# LARIX_V5_0.net
KiCad netlist of a schematic drawn in Altium Designer
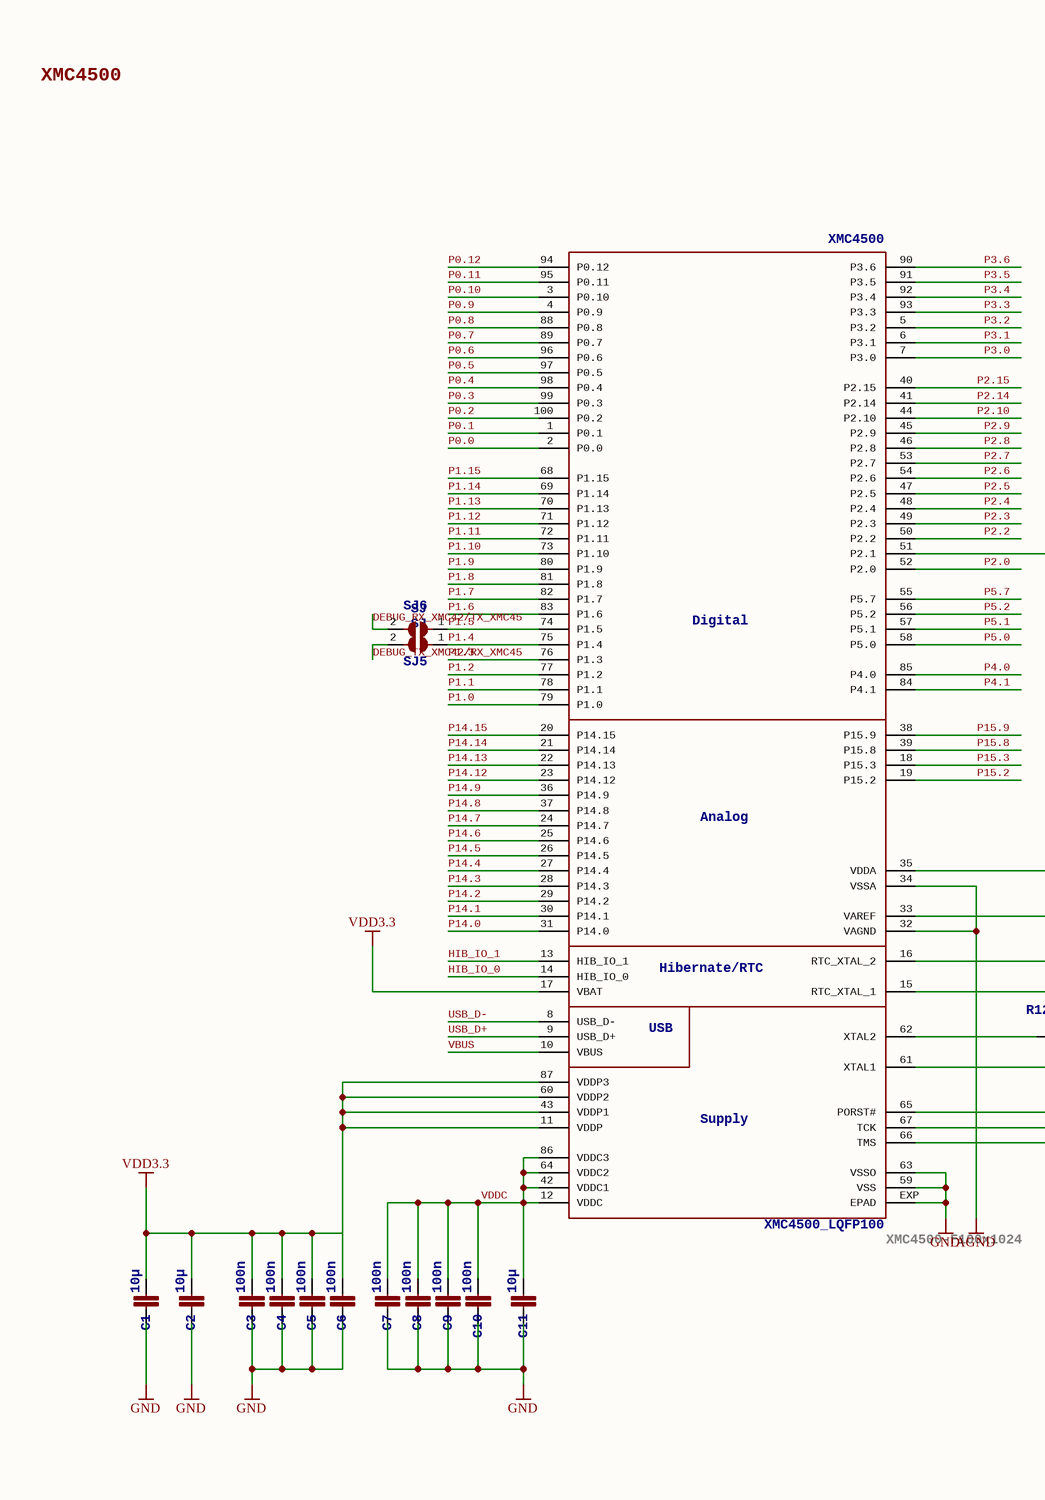
[diagram p0: LARIX_V5_0.SchDoc, left]
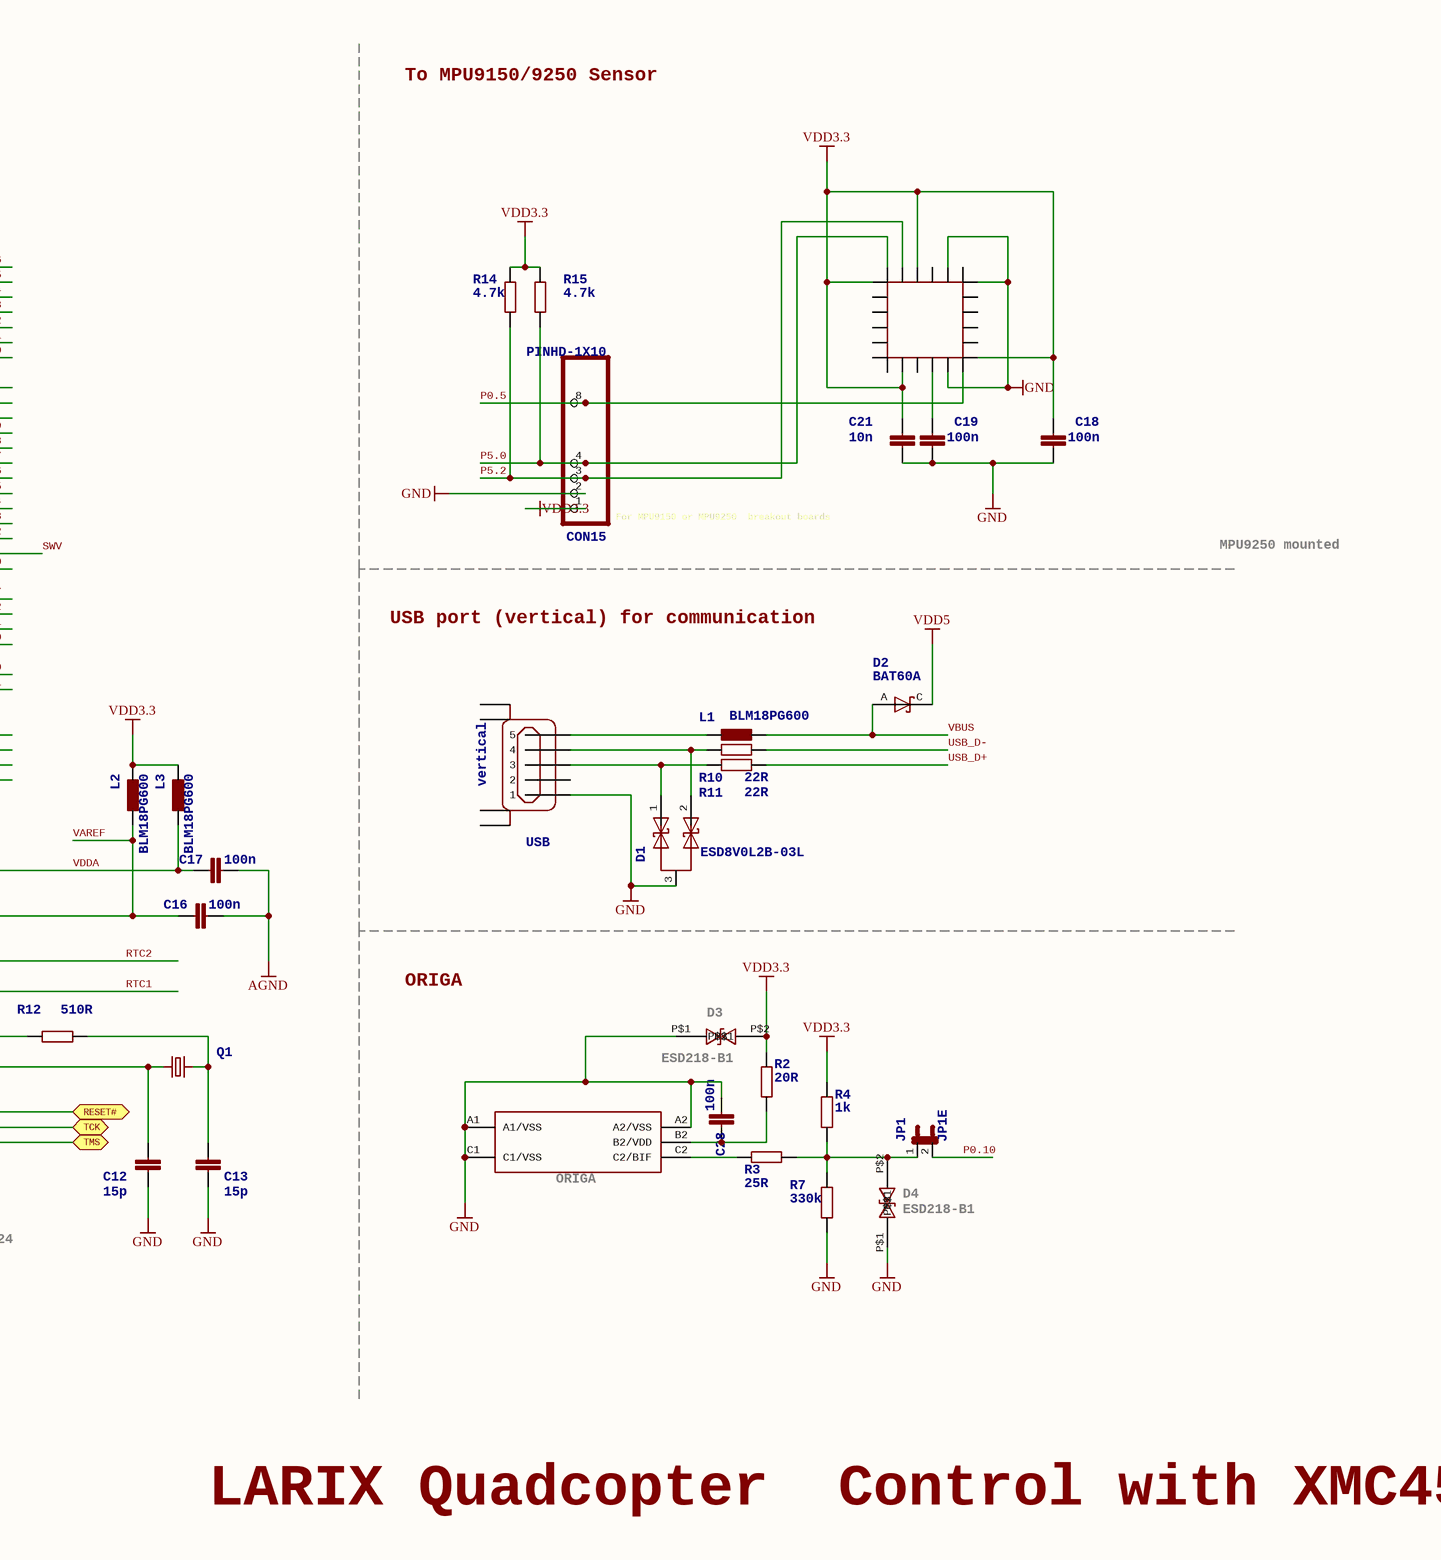
[diagram p1: LARIX_V5_0.SchDoc, right]

(export (version "E")
  (design (tool "Eeschema 10.0.6"))
  (components
    (comp (ref "C1")
      (value "10µ")
      (footprint "C0805K")
      (description "<B>CAPACITOR</B>, European symbol")
      (libsource (lib "libHMI_OLED-V1") (part "C-EUC0805K"))
    )
    (comp (ref "C2")
      (value "10µ")
      (footprint "C0805K")
      (description "<B>CAPACITOR</B>, European symbol")
      (libsource (lib "libHMI_OLED-V1") (part "C-EUC0805K"))
    )
    (comp (ref "C3")
      (value "100n")
      (footprint "C0603")
      (description "<B>CAPACITOR</B>, European symbol")
      (libsource (lib "libresistor") (part "C-EUC0603"))
    )
    (comp (ref "C4")
      (value "100n")
      (footprint "C0603")
      (description "<B>CAPACITOR</B>, European symbol")
      (libsource (lib "libresistor") (part "C-EUC0603"))
    )
    (comp (ref "C5")
      (value "100n")
      (footprint "C0603")
      (description "<B>CAPACITOR</B>, European symbol")
      (libsource (lib "libresistor") (part "C-EUC0603"))
    )
    (comp (ref "C6")
      (value "100n")
      (footprint "C0603")
      (description "<B>CAPACITOR</B>, European symbol")
      (libsource (lib "libresistor") (part "C-EUC0603"))
    )
    (comp (ref "C7")
      (value "100n")
      (footprint "C0603")
      (description "<B>CAPACITOR</B>, European symbol")
      (libsource (lib "libresistor") (part "C-EUC0603"))
    )
    (comp (ref "C8")
      (value "100n")
      (footprint "C0603")
      (description "<B>CAPACITOR</B>, European symbol")
      (libsource (lib "libresistor") (part "C-EUC0603"))
    )
    (comp (ref "C9")
      (value "100n")
      (footprint "C0603")
      (description "<B>CAPACITOR</B>, European symbol")
      (libsource (lib "libresistor") (part "C-EUC0603"))
    )
    (comp (ref "C10")
      (value "100n")
      (footprint "C0603")
      (description "<B>CAPACITOR</B>, European symbol")
      (libsource (lib "libresistor") (part "C-EUC0603"))
    )
    (comp (ref "C11")
      (value "10µ")
      (footprint "C0805K")
      (description "<B>CAPACITOR</B>, European symbol")
      (libsource (lib "libHMI_OLED-V1") (part "C-EUC0805K"))
    )
    (comp (ref "C12")
      (value "15p")
      (footprint "C0603")
      (description "<B>CAPACITOR</B>, European symbol")
      (libsource (lib "libresistor") (part "C-EUC0603"))
    )
    (comp (ref "C13")
      (value "15p")
      (footprint "C0603")
      (description "<B>CAPACITOR</B>, European symbol")
      (libsource (lib "libresistor") (part "C-EUC0603"))
    )
    (comp (ref "C16")
      (value "100n")
      (footprint "C0603")
      (description "<B>CAPACITOR</B>, European symbol")
      (libsource (lib "") (part "C-EUC0603_2"))
    )
    (comp (ref "C17")
      (value "100n")
      (footprint "C0603")
      (description "<B>CAPACITOR</B>, European symbol")
      (libsource (lib "") (part "C-EUC0603_2"))
    )
    (comp (ref "C18")
      (value "100n")
      (footprint "C0603")
      (description "<B>CAPACITOR</B>, European symbol")
      (libsource (lib "") (part "C-EUC0603_1"))
    )
    (comp (ref "C19")
      (value "100n")
      (footprint "C0603")
      (description "<B>CAPACITOR</B>, European symbol")
      (libsource (lib "") (part "C-EUC0603_1"))
    )
    (comp (ref "C21")
      (value "10n")
      (footprint "C0603")
      (description "<B>CAPACITOR</B>, European symbol")
      (libsource (lib "") (part "C-EUC0603_1"))
    )
    (comp (ref "C28")
      (value "100n")
      (footprint "C0603")
      (description "<B>CAPACITOR</B>, European symbol")
      (libsource (lib "libresistor") (part "C-EUC0603"))
    )
    (comp (ref "CON15")
      (value "PINHD-1X10")
      (footprint "1X10")
      (description "<b>PIN HEADER</b>")
      (fields (field (name ">NAME") "CON15") (field (name ">VALUE") "PINHD-1X10"))
      (libsource (lib "pinhead") (part "PINHD-1X10"))
    )
    (comp (ref "D1")
      (value "ESD8V0L2B-03L")
      (footprint "TSLP-3-1")
      (libsource (lib "libDsDiod") (part "ESD8V0L2B-03L"))
    )
    (comp (ref "D2") (value "BAT60A") (footprint "SOD323-R") (libsource (lib "libDsDiod") (part "BAT60")))
    (comp (ref "D3")
      (value "ESD218-B1-02EL")
      (footprint "TSLP-2-20")
      (libsource (lib "libESD218-B1") (part "ESD218-B1-02EL"))
    )
    (comp (ref "D4")
      (value "ESD218-B1-02EL")
      (footprint "TSLP-2-20")
      (libsource (lib "libESD218-B1") (part "ESD218-B1-02EL"))
    )
    (comp (ref "JP1")
      (value "JP1E")
      (footprint "JP1")
      (description "<b>JUMPER</b>")
      (fields (field (name ">NAME") "JP1") (field (name ">VALUE") "JP1E"))
      (libsource (lib "jumper") (part "JP1E"))
    )
    (comp (ref "L1") (value "BLM18PG600") (footprint "L1608") (libsource (lib "") (part "L_EU_L0603_1")))
    (comp (ref "L2")
      (value "BLM18PG600")
      (footprint "L1608")
      (fields (field (name ">NAME") "L2") (field (name ">VALUE") "BLM18PG600"))
      (libsource (lib "libPDFerr") (part "L_EU_L0603"))
    )
    (comp (ref "L3")
      (value "BLM18PG600")
      (footprint "L1608")
      (fields (field (name ">NAME") "L3") (field (name ">VALUE") "BLM18PG600"))
      (libsource (lib "libPDFerr") (part "L_EU_L0603"))
    )
    (comp (ref "MPU9250")
      (value "MPU9250")
      (footprint "QFN3X3-24+")
      (description "Herbys Model of a invensense 9250")
      (libsource (lib "invensense9250") (part "INVENSENSE9250HERBY"))
    )
    (comp (ref "ORIGA") (value "ORIGA2L") (footprint "WLB-5") (libsource (lib "libORIGA") (part "ORIGA2L")))
    (comp (ref "Q1")
      (value "12MHZ/S/3.2X2.5")
      (footprint "32X25_4PAD")
      (libsource (lib "libXMC4500_Relax-V1+USBvertical") (part "NX3225_2"))
    )
    (comp (ref "R2") (value "20R") (footprint "R0603") (libsource (lib "libDsR") (part "R-EU_R0603")))
    (comp (ref "R3") (value "25R") (footprint "R0603") (libsource (lib "libDsR") (part "R-EU_R0603")))
    (comp (ref "R4") (value "1k") (footprint "R0603") (libsource (lib "libDsR") (part "R-EU_R0603")))
    (comp (ref "R7") (value "330k") (footprint "R0603") (libsource (lib "libDsR") (part "R-EU_R0603")))
    (comp (ref "R10")
      (value "22R")
      (footprint "R0603")
      (description "<B>RESISTOR</B>, European symbol")
      (libsource (lib "libresistor") (part "R-EU_R0603"))
    )
    (comp (ref "R11")
      (value "22R")
      (footprint "R0603")
      (description "<B>RESISTOR</B>, European symbol")
      (libsource (lib "libresistor") (part "R-EU_R0603"))
    )
    (comp (ref "R12") (value "510R") (footprint "R0603") (libsource (lib "libDsR") (part "R-EU_R0603")))
    (comp (ref "R14")
      (value "4.7k")
      (footprint "R0603")
      (description "<B>RESISTOR</B>, European symbol")
      (libsource (lib "libresistor") (part "R-EU_R0603"))
    )
    (comp (ref "R15")
      (value "4.7k")
      (footprint "R0603")
      (description "<B>RESISTOR</B>, European symbol")
      (libsource (lib "libresistor") (part "R-EU_R0603"))
    )
    (comp (ref "SJ5")
      (value "SJ")
      (footprint "SJ")
      (description "SMD solder <b>JUMPER</b>")
      (libsource (lib "jumper") (part "SJ"))
    )
    (comp (ref "SJ6")
      (value "SJ")
      (footprint "SJ")
      (description "SMD solder <b>JUMPER</b>")
      (libsource (lib "jumper") (part "SJ"))
    )
    (comp (ref "USB")
      (value "vertical")
      (footprint "USBVERTICAL")
      (libsource (lib "libXMC4500_Relax-V1+USBvertical") (part "MICRO_USB_VERTICAL"))
    )
    (comp (ref "XMC4500")
      (value "XMC4500_LQFP100")
      (footprint "P/PG-LQFP-100-11")
      (fields
        (field (name ">NAME") "XMC4500")
        (field (name ">VALUE") "XMC4500_LQFP100")
        (field (name "USB") "USB")
        (field (name "SUPPLY") "Supply")
        (field (name "ANALOG") "Analog")
        (field (name "DIGITAL") "Digital")
        (field (name "HIBERNATE/RTC") "Hibernate/RTC")
      )
      (libsource (lib "libXMC4500_Relax-V1+USBvertical") (part "XMC4400_LQFP100"))
    )
  )
  (nets
    (net (code "1") (name "/DEBUG_RX_XMC42{slash}TX_XMC45") (class "Default")
      (node (ref "SJ6") (pin "2") (pinfunction "2_2") (pintype "passive"))
    )
    (net (code "2") (name "/DEBUG_TX_XMC42{slash}RX_XMC45") (class "Default")
      (node (ref "SJ5") (pin "2") (pinfunction "2_2") (pintype "passive"))
    )
    (net (code "3") (name "/HIB_IO_0") (class "Default")
      (node (ref "XMC4500") (pin "14") (pinfunction "HIB_IO_0_14") (pintype "passive"))
    )
    (net (code "4") (name "/HIB_IO_1") (class "Default")
      (node (ref "XMC4500") (pin "13") (pinfunction "HIB_IO_1_13") (pintype "passive"))
    )
    (net (code "5") (name "/P0.0") (class "Default")
      (node (ref "XMC4500") (pin "2") (pinfunction "P0.0_2") (pintype "passive"))
    )
    (net (code "6") (name "/P0.1") (class "Default")
      (node (ref "XMC4500") (pin "1") (pinfunction "P0.1_1") (pintype "passive"))
    )
    (net (code "7") (name "/P0.2") (class "Default")
      (node (ref "XMC4500") (pin "100") (pinfunction "P0.2_100") (pintype "passive"))
    )
    (net (code "8") (name "/P0.3") (class "Default")
      (node (ref "XMC4500") (pin "99") (pinfunction "P0.3_99") (pintype "passive"))
    )
    (net (code "9") (name "/P0.4") (class "Default")
      (node (ref "XMC4500") (pin "98") (pinfunction "P0.4_98") (pintype "passive"))
    )
    (net (code "10") (name "/P0.5") (class "Default")
      (node (ref "CON15") (pin "8") (pinfunction "8_8") (pintype "passive"))
      (node (ref "MPU9250") (pin "12") (pinfunction "12_12") (pintype "passive"))
      (node (ref "XMC4500") (pin "97") (pinfunction "P0.5_97") (pintype "passive"))
    )
    (net (code "11") (name "/P0.6") (class "Default")
      (node (ref "XMC4500") (pin "96") (pinfunction "P0.6_96") (pintype "passive"))
    )
    (net (code "12") (name "/P0.7") (class "Default")
      (node (ref "XMC4500") (pin "89") (pinfunction "P0.7_89") (pintype "passive"))
    )
    (net (code "13") (name "/P0.8") (class "Default")
      (node (ref "XMC4500") (pin "88") (pinfunction "P0.8_88") (pintype "passive"))
    )
    (net (code "14") (name "/P0.9") (class "Default")
      (node (ref "XMC4500") (pin "4") (pinfunction "P0.9_4") (pintype "passive"))
    )
    (net (code "15") (name "/P0.10") (class "Default")
      (node (ref "JP1") (pin "2") (pinfunction "2_2") (pintype "passive"))
      (node (ref "XMC4500") (pin "3") (pinfunction "P0.10_3") (pintype "passive"))
    )
    (net (code "16") (name "/P0.11") (class "Default")
      (node (ref "XMC4500") (pin "95") (pinfunction "P0.11_95") (pintype "passive"))
    )
    (net (code "17") (name "/P0.12") (class "Default")
      (node (ref "XMC4500") (pin "94") (pinfunction "P0.12_94") (pintype "passive"))
    )
    (net (code "18") (name "/P1.0") (class "Default")
      (node (ref "XMC4500") (pin "79") (pinfunction "P1.0_79") (pintype "passive"))
    )
    (net (code "19") (name "/P1.1") (class "Default")
      (node (ref "XMC4500") (pin "78") (pinfunction "P1.1_78") (pintype "passive"))
    )
    (net (code "20") (name "/P1.2") (class "Default")
      (node (ref "XMC4500") (pin "77") (pinfunction "P1.2_77") (pintype "passive"))
    )
    (net (code "21") (name "/P1.3") (class "Default")
      (node (ref "XMC4500") (pin "76") (pinfunction "P1.3_76") (pintype "passive"))
    )
    (net (code "22") (name "/P1.4") (class "Default")
      (node (ref "SJ5") (pin "1") (pinfunction "1_1") (pintype "passive"))
      (node (ref "XMC4500") (pin "75") (pinfunction "P1.4_75") (pintype "passive"))
    )
    (net (code "23") (name "/P1.5") (class "Default")
      (node (ref "SJ6") (pin "1") (pinfunction "1_1") (pintype "passive"))
      (node (ref "XMC4500") (pin "74") (pinfunction "P1.5_74") (pintype "passive"))
    )
    (net (code "24") (name "/P1.6") (class "Default")
      (node (ref "XMC4500") (pin "83") (pinfunction "P1.6_83") (pintype "passive"))
    )
    (net (code "25") (name "/P1.7") (class "Default")
      (node (ref "XMC4500") (pin "82") (pinfunction "P1.7_82") (pintype "passive"))
    )
    (net (code "26") (name "/P1.8") (class "Default")
      (node (ref "XMC4500") (pin "81") (pinfunction "P1.8_81") (pintype "passive"))
    )
    (net (code "27") (name "/P1.9") (class "Default")
      (node (ref "XMC4500") (pin "80") (pinfunction "P1.9_80") (pintype "passive"))
    )
    (net (code "28") (name "/P1.10") (class "Default")
      (node (ref "XMC4500") (pin "73") (pinfunction "P1.10_73") (pintype "passive"))
    )
    (net (code "29") (name "/P1.11") (class "Default")
      (node (ref "XMC4500") (pin "72") (pinfunction "P1.11_72") (pintype "passive"))
    )
    (net (code "30") (name "/P1.12") (class "Default")
      (node (ref "XMC4500") (pin "71") (pinfunction "P1.12_71") (pintype "passive"))
    )
    (net (code "31") (name "/P1.13") (class "Default")
      (node (ref "XMC4500") (pin "70") (pinfunction "P1.13_70") (pintype "passive"))
    )
    (net (code "32") (name "/P1.14") (class "Default")
      (node (ref "XMC4500") (pin "69") (pinfunction "P1.14_69") (pintype "passive"))
    )
    (net (code "33") (name "/P1.15") (class "Default")
      (node (ref "XMC4500") (pin "68") (pinfunction "P1.15_68") (pintype "passive"))
    )
    (net (code "34") (name "/P2.0") (class "Default")
      (node (ref "XMC4500") (pin "52") (pinfunction "P2.0_52") (pintype "passive"))
    )
    (net (code "35") (name "/P2.2") (class "Default")
      (node (ref "XMC4500") (pin "50") (pinfunction "P2.2_50") (pintype "passive"))
    )
    (net (code "36") (name "/P2.3") (class "Default")
      (node (ref "XMC4500") (pin "49") (pinfunction "P2.3_49") (pintype "passive"))
    )
    (net (code "37") (name "/P2.4") (class "Default")
      (node (ref "XMC4500") (pin "48") (pinfunction "P2.4_48") (pintype "passive"))
    )
    (net (code "38") (name "/P2.5") (class "Default")
      (node (ref "XMC4500") (pin "47") (pinfunction "P2.5_47") (pintype "passive"))
    )
    (net (code "39") (name "/P2.6") (class "Default")
      (node (ref "XMC4500") (pin "54") (pinfunction "P2.6_54") (pintype "passive"))
    )
    (net (code "40") (name "/P2.7") (class "Default")
      (node (ref "XMC4500") (pin "53") (pinfunction "P2.7_53") (pintype "passive"))
    )
    (net (code "41") (name "/P2.8") (class "Default")
      (node (ref "XMC4500") (pin "46") (pinfunction "P2.8_46") (pintype "passive"))
    )
    (net (code "42") (name "/P2.9") (class "Default")
      (node (ref "XMC4500") (pin "45") (pinfunction "P2.9_45") (pintype "passive"))
    )
    (net (code "43") (name "/P2.10") (class "Default")
      (node (ref "XMC4500") (pin "44") (pinfunction "P2.10_44") (pintype "passive"))
    )
    (net (code "44") (name "/P2.14") (class "Default")
      (node (ref "XMC4500") (pin "41") (pinfunction "P2.14_41") (pintype "passive"))
    )
    (net (code "45") (name "/P2.15") (class "Default")
      (node (ref "XMC4500") (pin "40") (pinfunction "P2.15_40") (pintype "passive"))
    )
    (net (code "46") (name "/P3.0") (class "Default")
      (node (ref "XMC4500") (pin "7") (pinfunction "P3.0_7") (pintype "passive"))
    )
    (net (code "47") (name "/P3.1") (class "Default")
      (node (ref "XMC4500") (pin "6") (pinfunction "P3.1_6") (pintype "passive"))
    )
    (net (code "48") (name "/P3.2") (class "Default")
      (node (ref "XMC4500") (pin "5") (pinfunction "P3.2_5") (pintype "passive"))
    )
    (net (code "49") (name "/P3.3") (class "Default")
      (node (ref "XMC4500") (pin "93") (pinfunction "P3.3_93") (pintype "passive"))
    )
    (net (code "50") (name "/P3.4") (class "Default")
      (node (ref "XMC4500") (pin "92") (pinfunction "P3.4_92") (pintype "passive"))
    )
    (net (code "51") (name "/P3.5") (class "Default")
      (node (ref "XMC4500") (pin "91") (pinfunction "P3.5_91") (pintype "passive"))
    )
    (net (code "52") (name "/P3.6") (class "Default")
      (node (ref "XMC4500") (pin "90") (pinfunction "P3.6_90") (pintype "passive"))
    )
    (net (code "53") (name "/P4.0") (class "Default")
      (node (ref "XMC4500") (pin "85") (pinfunction "P4.0_85") (pintype "passive"))
    )
    (net (code "54") (name "/P4.1") (class "Default")
      (node (ref "XMC4500") (pin "84") (pinfunction "P4.1_84") (pintype "passive"))
    )
    (net (code "55") (name "/P5.0") (class "Default")
      (node (ref "CON15") (pin "4") (pinfunction "4_4") (pintype "passive"))
      (node (ref "MPU9250") (pin "24") (pinfunction "24_24") (pintype "passive"))
      (node (ref "R15") (pin "1") (pinfunction "1_1") (pintype "passive"))
      (node (ref "XMC4500") (pin "58") (pinfunction "P5.0_58") (pintype "passive"))
    )
    (net (code "56") (name "/P5.1") (class "Default")
      (node (ref "XMC4500") (pin "57") (pinfunction "P5.1_57") (pintype "passive"))
    )
    (net (code "57") (name "/P5.2") (class "Default")
      (node (ref "CON15") (pin "3") (pinfunction "3_3") (pintype "passive"))
      (node (ref "MPU9250") (pin "23") (pinfunction "23_23") (pintype "passive"))
      (node (ref "R14") (pin "1") (pinfunction "1_1") (pintype "passive"))
      (node (ref "XMC4500") (pin "56") (pinfunction "P5.2_56") (pintype "passive"))
    )
    (net (code "58") (name "/P5.7") (class "Default")
      (node (ref "XMC4500") (pin "55") (pinfunction "P5.7_55") (pintype "passive"))
    )
    (net (code "59") (name "/P14.0") (class "Default")
      (node (ref "XMC4500") (pin "31") (pinfunction "P14.0_31") (pintype "passive"))
    )
    (net (code "60") (name "/P14.1") (class "Default")
      (node (ref "XMC4500") (pin "30") (pinfunction "P14.1_30") (pintype "passive"))
    )
    (net (code "61") (name "/P14.2") (class "Default")
      (node (ref "XMC4500") (pin "29") (pinfunction "P14.2_29") (pintype "passive"))
    )
    (net (code "62") (name "/P14.3") (class "Default")
      (node (ref "XMC4500") (pin "28") (pinfunction "P14.3_28") (pintype "passive"))
    )
    (net (code "63") (name "/P14.4") (class "Default")
      (node (ref "XMC4500") (pin "27") (pinfunction "P14.4_27") (pintype "passive"))
    )
    (net (code "64") (name "/P14.5") (class "Default")
      (node (ref "XMC4500") (pin "26") (pinfunction "P14.5_26") (pintype "passive"))
    )
    (net (code "65") (name "/P14.6") (class "Default")
      (node (ref "XMC4500") (pin "25") (pinfunction "P14.6_25") (pintype "passive"))
    )
    (net (code "66") (name "/P14.7") (class "Default")
      (node (ref "XMC4500") (pin "24") (pinfunction "P14.7_24") (pintype "passive"))
    )
    (net (code "67") (name "/P14.8") (class "Default")
      (node (ref "XMC4500") (pin "37") (pinfunction "P14.8_37") (pintype "passive"))
    )
    (net (code "68") (name "/P14.9") (class "Default")
      (node (ref "XMC4500") (pin "36") (pinfunction "P14.9_36") (pintype "passive"))
    )
    (net (code "69") (name "/P14.12") (class "Default")
      (node (ref "XMC4500") (pin "23") (pinfunction "P14.12_23") (pintype "passive"))
    )
    (net (code "70") (name "/P14.13") (class "Default")
      (node (ref "XMC4500") (pin "22") (pinfunction "P14.13_22") (pintype "passive"))
    )
    (net (code "71") (name "/P14.14") (class "Default")
      (node (ref "XMC4500") (pin "21") (pinfunction "P14.14_21") (pintype "passive"))
    )
    (net (code "72") (name "/P14.15") (class "Default")
      (node (ref "XMC4500") (pin "20") (pinfunction "P14.15_20") (pintype "passive"))
    )
    (net (code "73") (name "/P15.2") (class "Default")
      (node (ref "XMC4500") (pin "19") (pinfunction "P15.2_19") (pintype "passive"))
    )
    (net (code "74") (name "/P15.3") (class "Default")
      (node (ref "XMC4500") (pin "18") (pinfunction "P15.3_18") (pintype "passive"))
    )
    (net (code "75") (name "/P15.8") (class "Default")
      (node (ref "XMC4500") (pin "39") (pinfunction "P15.8_39") (pintype "passive"))
    )
    (net (code "76") (name "/P15.9") (class "Default")
      (node (ref "XMC4500") (pin "38") (pinfunction "P15.9_38") (pintype "passive"))
    )
    (net (code "77") (name "/RESET#") (class "Default")
      (node (ref "XMC4500") (pin "65") (pinfunction "PORST#_65") (pintype "passive"))
    )
    (net (code "78") (name "/RTC1") (class "Default")
      (node (ref "XMC4500") (pin "15") (pinfunction "RTC_XTAL_1_15") (pintype "passive"))
    )
    (net (code "79") (name "/RTC2") (class "Default")
      (node (ref "XMC4500") (pin "16") (pinfunction "RTC_XTAL_2_16") (pintype "passive"))
    )
    (net (code "80") (name "/SWV") (class "Default")
      (node (ref "XMC4500") (pin "51") (pinfunction "P2.1_51") (pintype "passive"))
    )
    (net (code "81") (name "/TCK") (class "Default")
      (node (ref "XMC4500") (pin "67") (pinfunction "TCK_67") (pintype "passive"))
    )
    (net (code "82") (name "/TMS") (class "Default")
      (node (ref "XMC4500") (pin "66") (pinfunction "TMS_66") (pintype "passive"))
    )
    (net (code "83") (name "/USB_D+") (class "Default")
      (node (ref "R11") (pin "2") (pinfunction "2_2") (pintype "passive"))
      (node (ref "XMC4500") (pin "9") (pinfunction "USB_D+_9") (pintype "passive"))
    )
    (net (code "84") (name "/USB_D-") (class "Default")
      (node (ref "R10") (pin "2") (pinfunction "2_2") (pintype "passive"))
      (node (ref "XMC4500") (pin "8") (pinfunction "USB_D-_8") (pintype "passive"))
    )
    (net (code "85") (name "/VAREF") (class "Default")
      (node (ref "C16") (pin "1") (pinfunction "1_1") (pintype "passive"))
      (node (ref "L2") (pin "1") (pinfunction "1_1") (pintype "passive"))
      (node (ref "XMC4500") (pin "33") (pinfunction "VAREF_33") (pintype "passive"))
    )
    (net (code "86") (name "/VBUS") (class "Default")
      (node (ref "D2") (pin "A") (pinfunction "A_A") (pintype "passive"))
      (node (ref "L1") (pin "1") (pinfunction "1_1") (pintype "passive"))
      (node (ref "XMC4500") (pin "10") (pinfunction "VBUS_10") (pintype "passive"))
    )
    (net (code "87") (name "/VDDA") (class "Default")
      (node (ref "C17") (pin "1") (pinfunction "1_1") (pintype "passive"))
      (node (ref "L3") (pin "1") (pinfunction "1_1") (pintype "passive"))
      (node (ref "XMC4500") (pin "35") (pinfunction "VDDA_35") (pintype "passive"))
    )
    (net (code "88") (name "/VDDC") (class "Default")
      (node (ref "C10") (pin "1") (pinfunction "1_1") (pintype "passive"))
      (node (ref "C11") (pin "1") (pinfunction "1_1") (pintype "passive"))
      (node (ref "C7") (pin "1") (pinfunction "1_1") (pintype "passive"))
      (node (ref "C8") (pin "1") (pinfunction "1_1") (pintype "passive"))
      (node (ref "C9") (pin "1") (pinfunction "1_1") (pintype "passive"))
      (node (ref "XMC4500") (pin "12") (pinfunction "VDDC_12") (pintype "passive"))
      (node (ref "XMC4500") (pin "42") (pinfunction "VDDC1_42") (pintype "passive"))
      (node (ref "XMC4500") (pin "64") (pinfunction "VDDC2_64") (pintype "passive"))
      (node (ref "XMC4500") (pin "86") (pinfunction "VDDC3_86") (pintype "passive"))
    )
    (net (code "89") (name "AGND") (class "Default")
      (node (ref "C16") (pin "2") (pinfunction "2_2") (pintype "passive"))
      (node (ref "C17") (pin "2") (pinfunction "2_2") (pintype "passive"))
      (node (ref "XMC4500") (pin "32") (pinfunction "VAGND_32") (pintype "passive"))
      (node (ref "XMC4500") (pin "34") (pinfunction "VSSA_34") (pintype "passive"))
    )
    (net (code "90") (name "GND") (class "Default")
      (node (ref "C1") (pin "2") (pinfunction "2_2") (pintype "passive"))
      (node (ref "C10") (pin "2") (pinfunction "2_2") (pintype "passive"))
      (node (ref "C11") (pin "2") (pinfunction "2_2") (pintype "passive"))
      (node (ref "C12") (pin "2") (pinfunction "2_2") (pintype "passive"))
      (node (ref "C13") (pin "2") (pinfunction "2_2") (pintype "passive"))
      (node (ref "C18") (pin "1") (pinfunction "1_1") (pintype "passive"))
      (node (ref "C19") (pin "1") (pinfunction "1_1") (pintype "passive"))
      (node (ref "C2") (pin "2") (pinfunction "2_2") (pintype "passive"))
      (node (ref "C21") (pin "1") (pinfunction "1_1") (pintype "passive"))
      (node (ref "C28") (pin "1") (pinfunction "1_1") (pintype "passive"))
      (node (ref "C3") (pin "2") (pinfunction "2_2") (pintype "passive"))
      (node (ref "C4") (pin "2") (pinfunction "2_2") (pintype "passive"))
      (node (ref "C5") (pin "2") (pinfunction "2_2") (pintype "passive"))
      (node (ref "C6") (pin "2") (pinfunction "2_2") (pintype "passive"))
      (node (ref "C7") (pin "2") (pinfunction "2_2") (pintype "passive"))
      (node (ref "C8") (pin "2") (pinfunction "2_2") (pintype "passive"))
      (node (ref "C9") (pin "2") (pinfunction "2_2") (pintype "passive"))
      (node (ref "CON15") (pin "2") (pinfunction "2_2") (pintype "passive"))
      (node (ref "D1") (pin "3") (pinfunction "3_3") (pintype "passive"))
      (node (ref "D3") (pin "P$1") (pinfunction "P$1_P$1") (pintype "passive"))
      (node (ref "D4") (pin "P$1") (pinfunction "P$1_P$1") (pintype "passive"))
      (node (ref "MPU9250") (pin "11") (pinfunction "11_11") (pintype "passive"))
      (node (ref "MPU9250") (pin "18") (pinfunction "18_18") (pintype "passive"))
      (node (ref "MPU9250") (pin "20") (pinfunction "20_20") (pintype "passive"))
      (node (ref "ORIGA") (pin "A1") (pinfunction "A1/VSS_A1") (pintype "passive"))
      (node (ref "ORIGA") (pin "A2") (pinfunction "A2/VSS_A2") (pintype "passive"))
      (node (ref "ORIGA") (pin "C1") (pinfunction "C1/VSS_C1") (pintype "passive"))
      (node (ref "R7") (pin "2") (pinfunction "2_2") (pintype "passive"))
      (node (ref "USB") (pin "1") (pinfunction "1_1") (pintype "passive"))
      (node (ref "XMC4500") (pin "59") (pinfunction "VSS_59") (pintype "passive"))
      (node (ref "XMC4500") (pin "63") (pinfunction "VSSO_63") (pintype "passive"))
      (node (ref "XMC4500") (pin "EXP") (pinfunction "EPAD_EXP") (pintype "passive"))
    )
    (net (code "91") (name "Net-(C19-Pad2)") (class "Default")
      (node (ref "C19") (pin "2") (pinfunction "2_2") (pintype "passive"))
      (node (ref "MPU9250") (pin "10") (pinfunction "10_10") (pintype "passive"))
    )
    (net (code "92") (name "Net-(D1-Pad2)") (class "Default")
      (node (ref "D1") (pin "2") (pinfunction "2_2") (pintype "passive"))
      (node (ref "R10") (pin "1") (pinfunction "1_1") (pintype "passive"))
      (node (ref "USB") (pin "4") (pinfunction "4_4") (pintype "passive"))
    )
    (net (code "93") (name "Net-(D4-PadP$2)") (class "Default")
      (node (ref "D4") (pin "P$2") (pinfunction "P$2_P$2") (pintype "passive"))
      (node (ref "JP1") (pin "1") (pinfunction "1_1") (pintype "passive"))
      (node (ref "R3") (pin "2") (pinfunction "2_2") (pintype "passive"))
      (node (ref "R4") (pin "2") (pinfunction "2_2") (pintype "passive"))
      (node (ref "R7") (pin "1") (pinfunction "1_1") (pintype "passive"))
    )
    (net (code "94") (name "Net-(L1-Pad2)") (class "Default")
      (node (ref "L1") (pin "2") (pinfunction "2_2") (pintype "passive"))
      (node (ref "USB") (pin "5") (pinfunction "5_5") (pintype "passive"))
    )
    (net (code "95") (name "Net-(ORIGA-B2{slash}VDD)") (class "Default")
      (node (ref "C28") (pin "2") (pinfunction "2_2") (pintype "passive"))
      (node (ref "ORIGA") (pin "B2") (pinfunction "B2/VDD_B2") (pintype "passive"))
      (node (ref "R2") (pin "2") (pinfunction "2_2") (pintype "passive"))
    )
    (net (code "96") (name "Net-(ORIGA-C2{slash}BIF)") (class "Default")
      (node (ref "ORIGA") (pin "C2") (pinfunction "C2/BIF_C2") (pintype "passive"))
      (node (ref "R3") (pin "1") (pinfunction "1_1") (pintype "passive"))
    )
    (net (code "97") (name "Net-(Q1-2)") (class "Default")
      (node (ref "C13") (pin "1") (pinfunction "1_1") (pintype "passive"))
      (node (ref "Q1") (pin "3") (pinfunction "2_3") (pintype "passive"))
      (node (ref "R12") (pin "2") (pinfunction "2_2") (pintype "passive"))
    )
    (net (code "98") (name "Net-(USB-3)") (class "Default")
      (node (ref "D1") (pin "1") (pinfunction "1_1") (pintype "passive"))
      (node (ref "R11") (pin "1") (pinfunction "1_1") (pintype "passive"))
      (node (ref "USB") (pin "3+") (pinfunction "3_3+") (pintype "passive"))
    )
    (net (code "99") (name "Net-(XMC4500-XTAL1)") (class "Default")
      (node (ref "C12") (pin "1") (pinfunction "1_1") (pintype "passive"))
      (node (ref "Q1") (pin "1") (pinfunction "1_1") (pintype "passive"))
      (node (ref "XMC4500") (pin "61") (pinfunction "XTAL1_61") (pintype "passive"))
    )
    (net (code "100") (name "Net-(XMC4500-XTAL2)") (class "Default")
      (node (ref "R12") (pin "1") (pinfunction "1_1") (pintype "passive"))
      (node (ref "XMC4500") (pin "62") (pinfunction "XTAL2_62") (pintype "passive"))
    )
    (net (code "101") (name "VDD3.3") (class "Default")
      (node (ref "C1") (pin "1") (pinfunction "1_1") (pintype "passive"))
      (node (ref "C18") (pin "2") (pinfunction "2_2") (pintype "passive"))
      (node (ref "C2") (pin "1") (pinfunction "1_1") (pintype "passive"))
      (node (ref "C21") (pin "2") (pinfunction "2_2") (pintype "passive"))
      (node (ref "C3") (pin "1") (pinfunction "1_1") (pintype "passive"))
      (node (ref "C4") (pin "1") (pinfunction "1_1") (pintype "passive"))
      (node (ref "C5") (pin "1") (pinfunction "1_1") (pintype "passive"))
      (node (ref "C6") (pin "1") (pinfunction "1_1") (pintype "passive"))
      (node (ref "CON15") (pin "1") (pinfunction "1_1") (pintype "passive"))
      (node (ref "D3") (pin "P$2") (pinfunction "P$2_P$2") (pintype "passive"))
      (node (ref "L2") (pin "2") (pinfunction "2_2") (pintype "passive"))
      (node (ref "L3") (pin "2") (pinfunction "2_2") (pintype "passive"))
      (node (ref "MPU9250") (pin "1") (pinfunction "1_1") (pintype "passive"))
      (node (ref "MPU9250") (pin "13") (pinfunction "13_13") (pintype "passive"))
      (node (ref "MPU9250") (pin "22") (pinfunction "22_22") (pintype "passive"))
      (node (ref "MPU9250") (pin "8") (pinfunction "8_8") (pintype "passive"))
      (node (ref "R14") (pin "2") (pinfunction "2_2") (pintype "passive"))
      (node (ref "R15") (pin "2") (pinfunction "2_2") (pintype "passive"))
      (node (ref "R2") (pin "1") (pinfunction "1_1") (pintype "passive"))
      (node (ref "R4") (pin "1") (pinfunction "1_1") (pintype "passive"))
      (node (ref "XMC4500") (pin "11") (pinfunction "VDDP_11") (pintype "passive"))
      (node (ref "XMC4500") (pin "17") (pinfunction "VBAT_17") (pintype "passive"))
      (node (ref "XMC4500") (pin "43") (pinfunction "VDDP1_43") (pintype "passive"))
      (node (ref "XMC4500") (pin "60") (pinfunction "VDDP2_60") (pintype "passive"))
      (node (ref "XMC4500") (pin "87") (pinfunction "VDDP3_87") (pintype "passive"))
    )
    (net (code "102") (name "VDD5") (class "Default")
      (node (ref "D2") (pin "C") (pinfunction "C_C") (pintype "passive"))
    )
    (net (code "103") (name "unconnected-(MPU9250-Pad2)") (class "Default")
      (node (ref "MPU9250") (pin "2") (pinfunction "2_2") (pintype "passive"))
    )
    (net (code "104") (name "unconnected-(MPU9250-Pad3)") (class "Default")
      (node (ref "MPU9250") (pin "3") (pinfunction "3_3") (pintype "passive"))
    )
    (net (code "105") (name "unconnected-(MPU9250-Pad4)") (class "Default")
      (node (ref "MPU9250") (pin "4") (pinfunction "4_4") (pintype "passive"))
    )
    (net (code "106") (name "unconnected-(MPU9250-Pad5)") (class "Default")
      (node (ref "MPU9250") (pin "5") (pinfunction "5_5") (pintype "passive"))
    )
    (net (code "107") (name "unconnected-(MPU9250-Pad6)") (class "Default")
      (node (ref "MPU9250") (pin "6") (pinfunction "6_6") (pintype "passive"))
    )
    (net (code "108") (name "unconnected-(MPU9250-Pad7)") (class "Default")
      (node (ref "MPU9250") (pin "7") (pinfunction "7_7") (pintype "passive"))
    )
    (net (code "109") (name "unconnected-(MPU9250-Pad9)") (class "Default")
      (node (ref "MPU9250") (pin "9") (pinfunction "9_9") (pintype "passive"))
    )
    (net (code "110") (name "unconnected-(MPU9250-Pad14)") (class "Default")
      (node (ref "MPU9250") (pin "14") (pinfunction "14_14") (pintype "passive"))
    )
    (net (code "111") (name "unconnected-(MPU9250-Pad15)") (class "Default")
      (node (ref "MPU9250") (pin "15") (pinfunction "15_15") (pintype "passive"))
    )
    (net (code "112") (name "unconnected-(MPU9250-Pad16)") (class "Default")
      (node (ref "MPU9250") (pin "16") (pinfunction "16_16") (pintype "passive"))
    )
    (net (code "113") (name "unconnected-(MPU9250-Pad17)") (class "Default")
      (node (ref "MPU9250") (pin "17") (pinfunction "17_17") (pintype "passive"))
    )
    (net (code "114") (name "unconnected-(MPU9250-Pad19)") (class "Default")
      (node (ref "MPU9250") (pin "19") (pinfunction "19_19") (pintype "passive"))
    )
    (net (code "115") (name "unconnected-(MPU9250-Pad21)") (class "Default")
      (node (ref "MPU9250") (pin "21") (pinfunction "21_21") (pintype "passive"))
    )
    (net (code "116") (name "unconnected-(USB-PGH1-PadP$1)") (class "Default")
      (node (ref "USB") (pin "P$1") (pinfunction "PGH1_P$1") (pintype "passive"))
    )
    (net (code "117") (name "unconnected-(USB-PGH2-PadP$2)") (class "Default")
      (node (ref "USB") (pin "P$2") (pinfunction "PGH2_P$2") (pintype "passive"))
    )
    (net (code "118") (name "unconnected-(USB-PGH3-PadP$3)") (class "Default")
      (node (ref "USB") (pin "P$3") (pinfunction "PGH3_P$3") (pintype "passive"))
    )
    (net (code "119") (name "unconnected-(USB-PGH4-PadP$4)") (class "Default")
      (node (ref "USB") (pin "P$4") (pinfunction "PGH4_P$4") (pintype "passive"))
    )
    (net (code "120") (name "unconnected-(USB-Pad2)") (class "Default")
      (node (ref "USB") (pin "2") (pinfunction "2_2") (pintype "passive"))
    )
  )
)
